# neke_blokade.net
KiCad netlist of a schematic drawn in Altium Designer
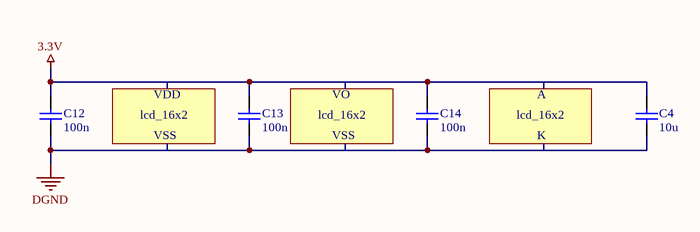
[diagram p0: neke_blokade.SchDoc]

(export (version "E")
  (design (tool "Eeschema 10.0.6"))
  (components
    (comp (ref "C4")
      (value "10u")
      (footprint "6-0805_N")
      (description "Keramički kondezator")
      (libsource (lib "Miscellaneous Devices") (part "Cap"))
    )
    (comp (ref "C12")
      (value "100n")
      (footprint "6-0805_N")
      (description "Keramički kondezator")
      (libsource (lib "Miscellaneous Devices") (part "Cap"))
    )
    (comp (ref "C13")
      (value "100n")
      (footprint "6-0805_N")
      (description "Keramički kondezator")
      (libsource (lib "Miscellaneous Devices") (part "Cap"))
    )
    (comp (ref "C14")
      (value "100n")
      (footprint "6-0805_N")
      (description "Keramički kondezator")
      (libsource (lib "Miscellaneous Devices") (part "Cap"))
    )
  )
  (nets
    (net (code "1") (name "3.3V") (class "Default")
      (node (ref "C12") (pin "2") (pinfunction "2_2") (pintype "passive"))
      (node (ref "C13") (pin "2") (pinfunction "2_2") (pintype "passive"))
      (node (ref "C14") (pin "2") (pinfunction "2_2") (pintype "passive"))
      (node (ref "C4") (pin "2") (pinfunction "2_2") (pintype "passive"))
    )
    (net (code "2") (name "DGND") (class "Default")
      (node (ref "C12") (pin "1") (pinfunction "1_1") (pintype "passive"))
      (node (ref "C13") (pin "1") (pinfunction "1_1") (pintype "passive"))
      (node (ref "C14") (pin "1") (pinfunction "1_1") (pintype "passive"))
      (node (ref "C4") (pin "1") (pinfunction "1_1") (pintype "passive"))
    )
  )
)
